# dc.net
KiCad netlist of a schematic drawn in EAGLE
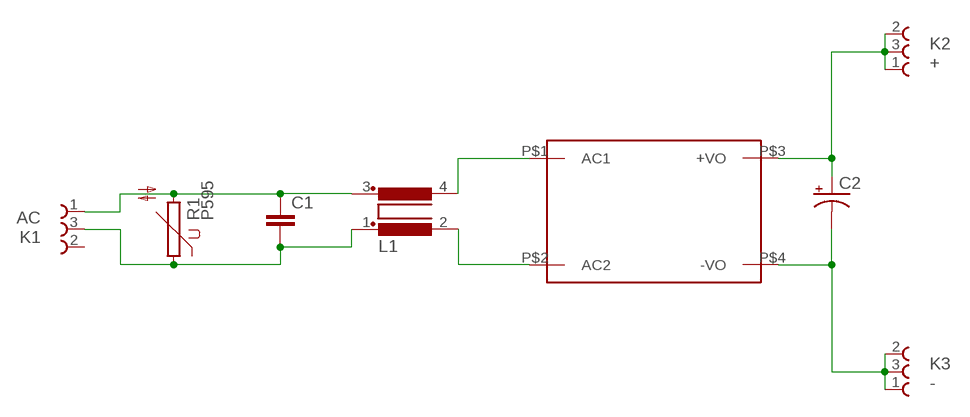
[diagram p0: schematic, sheet 1]

(export (version "E")
  (design (tool "Eeschema 10.0.6"))
  (components
    (comp (ref "C1")
      (value "C15/7")
      (footprint "eagle-import:C15B7")
      (libsource (lib "eagle-import") (part "C15/7"))
    )
    (comp (ref "C2")
      (value "CPOL-USE10-20")
      (footprint "eagle-import:EB20D")
      (libsource (lib "eagle-import") (part "CPOL-USE10-20"))
    )
    (comp (ref "K1")
      (value "AC")
      (footprint "eagle-import:691218410003")
      (libsource (lib "eagle-import") (part "691218410003"))
    )
    (comp (ref "K2")
      (value "+")
      (footprint "eagle-import:691218410003")
      (libsource (lib "eagle-import") (part "691218410003"))
    )
    (comp (ref "K3")
      (value "-")
      (footprint "eagle-import:691218410003")
      (libsource (lib "eagle-import") (part "691218410003"))
    )
    (comp (ref "L1")
      (value "R1003UB5")
      (footprint "eagle-import:B5")
      (libsource (lib "eagle-import") (part "R1003UB5"))
    )
    (comp (ref "R1")
      (value "P595")
      (footprint "eagle-import:P595")
      (libsource (lib "eagle-import") (part "P595"))
    )
    (comp (ref "U$1")
      (value "HLK-PM03HLK-20M")
      (footprint "eagle-import:HLK-20M")
      (libsource (lib "eagle-import") (part "HLK-PM03HLK-20M"))
    )
  )
  (nets
    (net (code "1") (name "Net-(K1-2)") (class "Default")
      (node (ref "C1") (pin "2") (pinfunction "2_2") (pintype "passive"))
      (node (ref "K1") (pin "3") (pinfunction "2_3") (pintype "passive"))
      (node (ref "L1") (pin "1") (pinfunction "1_1") (pintype "passive"))
      (node (ref "R1") (pin "1") (pinfunction "1_1") (pintype "passive"))
    )
    (net (code "2") (name "Net-(K1-3)") (class "Default")
      (node (ref "C1") (pin "1") (pinfunction "1_1") (pintype "passive"))
      (node (ref "K1") (pin "1") (pinfunction "3_1") (pintype "passive"))
      (node (ref "L1") (pin "3") (pinfunction "3_3") (pintype "passive"))
      (node (ref "R1") (pin "2") (pinfunction "2_2") (pintype "passive"))
    )
    (net (code "3") (name "Net-(K2-1)") (class "Default")
      (node (ref "C2") (pin "+") (pinfunction "+_+") (pintype "passive"))
      (node (ref "K2") (pin "1") (pinfunction "3_1") (pintype "passive"))
      (node (ref "K2") (pin "2") (pinfunction "1_2") (pintype "passive"))
      (node (ref "K2") (pin "3") (pinfunction "2_3") (pintype "passive"))
      (node (ref "U$1") (pin "P$3") (pinfunction "+VO_P$3") (pintype "bidirectional"))
    )
    (net (code "4") (name "Net-(K3-1)") (class "Default")
      (node (ref "C2") (pin "-") (pinfunction "-_-") (pintype "passive"))
      (node (ref "K3") (pin "1") (pinfunction "3_1") (pintype "passive"))
      (node (ref "K3") (pin "2") (pinfunction "1_2") (pintype "passive"))
      (node (ref "K3") (pin "3") (pinfunction "2_3") (pintype "passive"))
      (node (ref "U$1") (pin "P$4") (pinfunction "-VO_P$4") (pintype "bidirectional"))
    )
    (net (code "5") (name "Net-(U$1-AC1)") (class "Default")
      (node (ref "L1") (pin "4") (pinfunction "4_4") (pintype "passive"))
      (node (ref "U$1") (pin "P$1") (pinfunction "AC1_P$1") (pintype "bidirectional"))
    )
    (net (code "6") (name "Net-(U$1-AC2)") (class "Default")
      (node (ref "L1") (pin "2") (pinfunction "2_2") (pintype "passive"))
      (node (ref "U$1") (pin "P$2") (pinfunction "AC2_P$2") (pintype "bidirectional"))
    )
    (net (code "7") (name "unconnected-(K1-1-Pad2)") (class "Default")
      (node (ref "K1") (pin "2") (pinfunction "1_2") (pintype "passive"))
    )
  )
)
